# mb.net
KiCad netlist of a schematic drawn in EAGLE
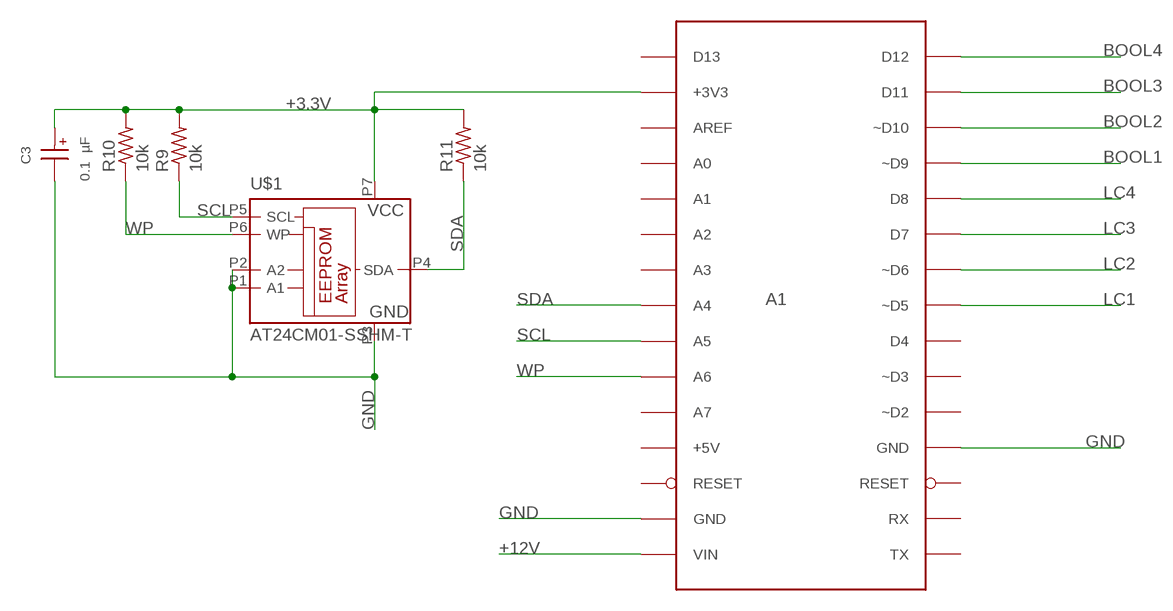
[diagram p0: schematic, sheet 1]
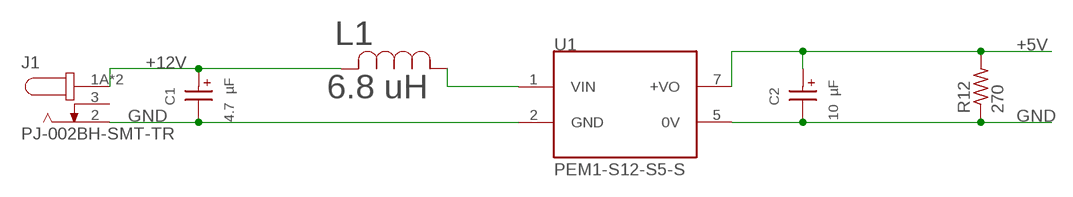
[diagram p1: schematic, sheet 2]
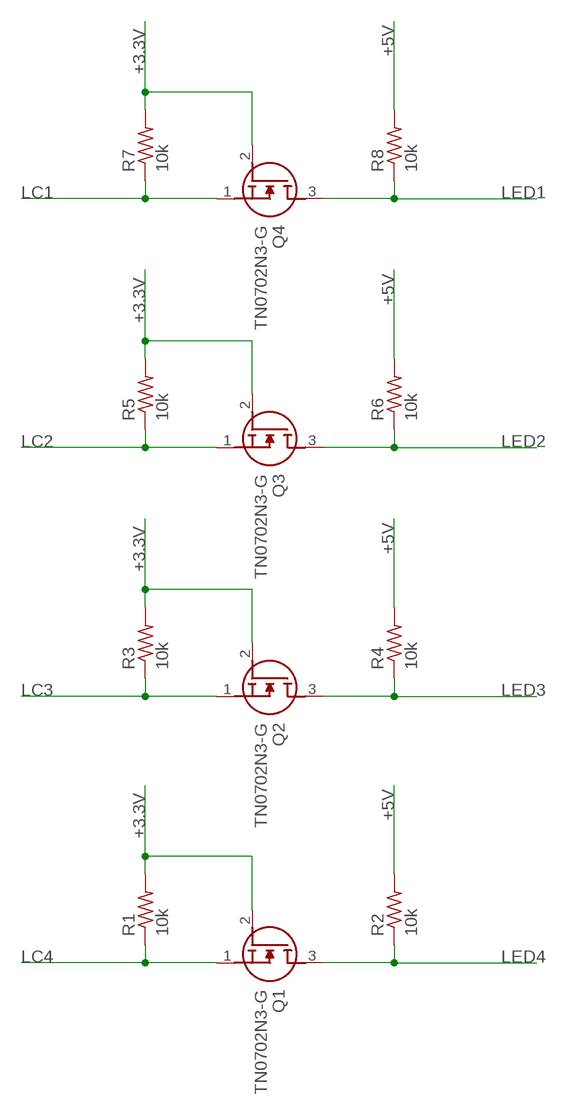
[diagram p2: schematic, sheet 3]
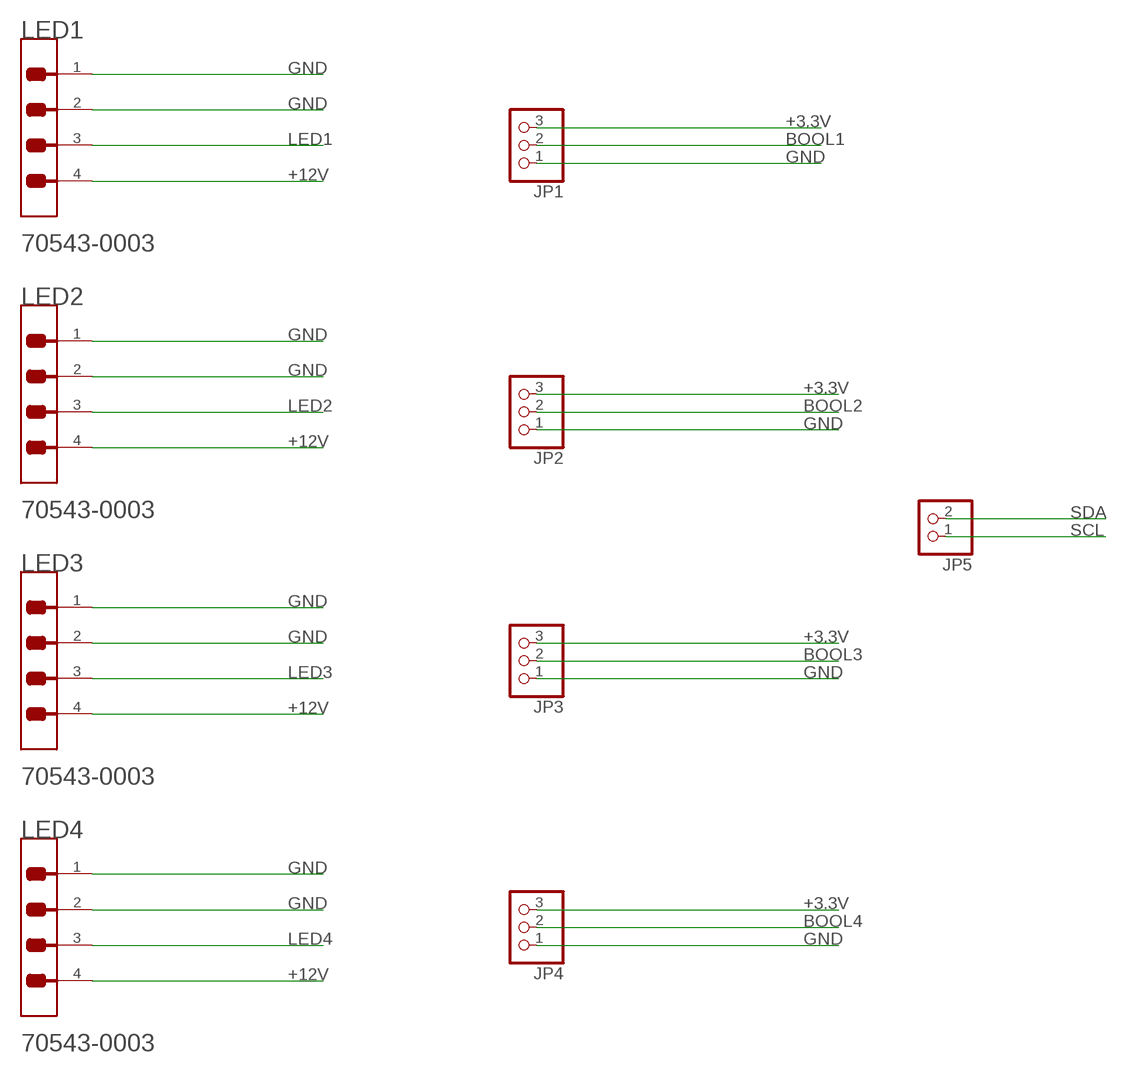
[diagram p3: schematic, sheet 4]

(export (version "E")
  (design (tool "Eeschema 10.0.6"))
  (components
    (comp (ref "Q1")
      (value "TN0702N3-G")
      (footprint "eagle-import:LND150N3-G")
      (fields (field (name "MOUSER_PART_NUMBER") "689-TN0702N3-G"))
      (libsource (lib "eagle-import") (part "TN0702N3-G"))
    )
    (comp (ref "Q2")
      (value "TN0702N3-G")
      (footprint "eagle-import:LND150N3-G")
      (fields (field (name "MOUSER_PART_NUMBER") "689-TN0702N3-G"))
      (libsource (lib "eagle-import") (part "TN0702N3-G"))
    )
    (comp (ref "Q3")
      (value "TN0702N3-G")
      (footprint "eagle-import:LND150N3-G")
      (fields (field (name "MOUSER_PART_NUMBER") "689-TN0702N3-G"))
      (libsource (lib "eagle-import") (part "TN0702N3-G"))
    )
    (comp (ref "Q4")
      (value "TN0702N3-G")
      (footprint "eagle-import:LND150N3-G")
      (fields (field (name "MOUSER_PART_NUMBER") "689-TN0702N3-G"))
      (libsource (lib "eagle-import") (part "TN0702N3-G"))
    )
    (comp (ref "R1")
      (value "10k")
      (footprint "eagle-import:CFR-25")
      (libsource (lib "eagle-import") (part "YAGEO-CFR-25"))
    )
    (comp (ref "R2")
      (value "10k")
      (footprint "eagle-import:CFR-25")
      (libsource (lib "eagle-import") (part "YAGEO-CFR-25"))
    )
    (comp (ref "R3")
      (value "10k")
      (footprint "eagle-import:CFR-25")
      (libsource (lib "eagle-import") (part "YAGEO-CFR-25"))
    )
    (comp (ref "R4")
      (value "10k")
      (footprint "eagle-import:CFR-25")
      (libsource (lib "eagle-import") (part "YAGEO-CFR-25"))
    )
    (comp (ref "R5")
      (value "10k")
      (footprint "eagle-import:CFR-25")
      (libsource (lib "eagle-import") (part "YAGEO-CFR-25"))
    )
    (comp (ref "R6")
      (value "10k")
      (footprint "eagle-import:CFR-25")
      (libsource (lib "eagle-import") (part "YAGEO-CFR-25"))
    )
    (comp (ref "R7")
      (value "10k")
      (footprint "eagle-import:CFR-25")
      (libsource (lib "eagle-import") (part "YAGEO-CFR-25"))
    )
    (comp (ref "R8")
      (value "10k")
      (footprint "eagle-import:CFR-25")
      (libsource (lib "eagle-import") (part "YAGEO-CFR-25"))
    )
    (comp (ref "C1")
      (value "4.7 µF")
      (footprint "eagle-import:WCAP-ATG5_5X11(DXL)")
      (libsource (lib "eagle-import") (part "WCAP-ATG5_5X11_860020672008"))
    )
    (comp (ref "C2")
      (value "10 µF")
      (footprint "eagle-import:WCAP-ATG5_5X11(DXL)")
      (libsource (lib "eagle-import") (part "WCAP-ATG5_5X11_860020672010"))
    )
    (comp (ref "J1")
      (value "PJ-002BH-SMT-TR")
      (footprint "eagle-import:CUI_PJ-002BH-SMT-TR")
      (fields (field (name "MANUFACTURER") "CUI INC"))
      (libsource (lib "eagle-import") (part "PJ-002BH-SMT-TR"))
    )
    (comp (ref "L1")
      (value "6.8 uH")
      (footprint "eagle-import:RL622_SERIES")
      (fields (field (name "MANUFACTURER_PART_NUMBER") "RL622-4R7K-RC"))
      (libsource (lib "eagle-import") (part "RL622-6R8K-RC"))
    )
    (comp (ref "R12")
      (value "270")
      (footprint "eagle-import:CFR-25")
      (libsource (lib "eagle-import") (part "YAGEO-CFR-25"))
    )
    (comp (ref "U1")
      (value "PEM1-S12-S5-S")
      (footprint "eagle-import:CONV_PEM1-S12-S5-S")
      (fields (field (name "MF") "CUI") (field (name "MP") "PEM1-S12-S12-S"))
      (libsource (lib "eagle-import") (part "PEM1-S12-S5-S"))
    )
    (comp (ref "A1")
      (value "NANO_33_IOTNANO_EVERY_SMD")
      (footprint "eagle-import:NANO_EVERY_SMD_PADS")
      (libsource (lib "eagle-import") (part "NANO_33_IOTNANO_EVERY_SMD"))
    )
    (comp (ref "C3")
      (value "0.1 µF")
      (footprint "eagle-import:WCAP-ATG5_5X11(DXL)")
      (libsource (lib "eagle-import") (part "WCAP-ATG5_5X11_860020672001"))
    )
    (comp (ref "R9")
      (value "10k")
      (footprint "eagle-import:CFR-25")
      (libsource (lib "eagle-import") (part "YAGEO-CFR-25"))
    )
    (comp (ref "R10")
      (value "10k")
      (footprint "eagle-import:CFR-25")
      (libsource (lib "eagle-import") (part "YAGEO-CFR-25"))
    )
    (comp (ref "R11")
      (value "10k")
      (footprint "eagle-import:CFR-25")
      (libsource (lib "eagle-import") (part "YAGEO-CFR-25"))
    )
    (comp (ref "U$1")
      (value "AT24CM01-SSHM-T")
      (footprint "eagle-import:8-SOIC(3.9MM)")
      (libsource (lib "eagle-import") (part "AT24CM01-SSHM-T"))
    )
    (comp (ref "JP1")
      (value "PINHD-1X3/90")
      (footprint "eagle-import:1X03_90")
      (libsource (lib "eagle-import") (part "PINHD-1X3/90"))
    )
    (comp (ref "JP2")
      (value "PINHD-1X3/90")
      (footprint "eagle-import:1X03_90")
      (libsource (lib "eagle-import") (part "PINHD-1X3/90"))
    )
    (comp (ref "JP3")
      (value "PINHD-1X3/90")
      (footprint "eagle-import:1X03_90")
      (libsource (lib "eagle-import") (part "PINHD-1X3/90"))
    )
    (comp (ref "JP4")
      (value "PINHD-1X3/90")
      (footprint "eagle-import:1X03_90")
      (libsource (lib "eagle-import") (part "PINHD-1X3/90"))
    )
    (comp (ref "JP5")
      (value "PINHD-1X2")
      (footprint "eagle-import:1X02")
      (libsource (lib "eagle-import") (part "PINHD-1X2"))
    )
    (comp (ref "LED1")
      (value "MOLEX_70543-0003MOLEX_70543-0003_0_0")
      (footprint "eagle-import:MOLEX_70543-0003_0")
      (fields
        (field (name "DIGIKEY_PART_NUMBER") "WM4802-ND")
        (field (name "MF") "Molex")
        (field (name "MOUSER_PART_NUMBER") "538-70543-0003")
      )
      (libsource (lib "eagle-import") (part "MOLEX_70543-0003MOLEX_70543-0003_0_0"))
    )
    (comp (ref "LED2")
      (value "MOLEX_70543-0003MOLEX_70543-0003_0_0")
      (footprint "eagle-import:MOLEX_70543-0003_0")
      (fields
        (field (name "DIGIKEY_PART_NUMBER") "WM4802-ND")
        (field (name "MF") "Molex")
        (field (name "MOUSER_PART_NUMBER") "538-70543-0003")
      )
      (libsource (lib "eagle-import") (part "MOLEX_70543-0003MOLEX_70543-0003_0_0"))
    )
    (comp (ref "LED3")
      (value "MOLEX_70543-0003MOLEX_70543-0003_0_0")
      (footprint "eagle-import:MOLEX_70543-0003_0")
      (fields
        (field (name "DIGIKEY_PART_NUMBER") "WM4802-ND")
        (field (name "MF") "Molex")
        (field (name "MOUSER_PART_NUMBER") "538-70543-0003")
      )
      (libsource (lib "eagle-import") (part "MOLEX_70543-0003MOLEX_70543-0003_0_0"))
    )
    (comp (ref "LED4")
      (value "MOLEX_70543-0003MOLEX_70543-0003_0_0")
      (footprint "eagle-import:MOLEX_70543-0003_0")
      (fields
        (field (name "DIGIKEY_PART_NUMBER") "WM4802-ND")
        (field (name "MF") "Molex")
        (field (name "MOUSER_PART_NUMBER") "538-70543-0003")
      )
      (libsource (lib "eagle-import") (part "MOLEX_70543-0003MOLEX_70543-0003_0_0"))
    )
  )
  (nets
    (net (code "1") (name "+3.3V") (class "Default")
      (node (ref "A1") (pin "+3.3V") (pinfunction "+3V3_+3.3V") (pintype "output"))
      (node (ref "C3") (pin "1") (pinfunction "+_1") (pintype "passive"))
      (node (ref "JP1") (pin "3") (pinfunction "3_3") (pintype "passive"))
      (node (ref "JP2") (pin "3") (pinfunction "3_3") (pintype "passive"))
      (node (ref "JP3") (pin "3") (pinfunction "3_3") (pintype "passive"))
      (node (ref "JP4") (pin "3") (pinfunction "3_3") (pintype "passive"))
      (node (ref "Q1") (pin "2") (pinfunction "G_2") (pintype "bidirectional"))
      (node (ref "Q2") (pin "2") (pinfunction "G_2") (pintype "bidirectional"))
      (node (ref "Q3") (pin "2") (pinfunction "G_2") (pintype "bidirectional"))
      (node (ref "Q4") (pin "2") (pinfunction "G_2") (pintype "bidirectional"))
      (node (ref "R1") (pin "P$2") (pinfunction "2_P$2") (pintype "passive"))
      (node (ref "R10") (pin "P$2") (pinfunction "2_P$2") (pintype "passive"))
      (node (ref "R11") (pin "P$2") (pinfunction "2_P$2") (pintype "passive"))
      (node (ref "R3") (pin "P$2") (pinfunction "2_P$2") (pintype "passive"))
      (node (ref "R5") (pin "P$2") (pinfunction "2_P$2") (pintype "passive"))
      (node (ref "R7") (pin "P$2") (pinfunction "2_P$2") (pintype "passive"))
      (node (ref "R9") (pin "P$2") (pinfunction "2_P$2") (pintype "passive"))
      (node (ref "U$1") (pin "P7") (pinfunction "VCC_P7") (pintype "power_in"))
    )
    (net (code "2") (name "+5V") (class "Default")
      (node (ref "C2") (pin "1") (pinfunction "+_1") (pintype "passive"))
      (node (ref "R12") (pin "P$2") (pinfunction "2_P$2") (pintype "passive"))
      (node (ref "R2") (pin "P$2") (pinfunction "2_P$2") (pintype "passive"))
      (node (ref "R4") (pin "P$2") (pinfunction "2_P$2") (pintype "passive"))
      (node (ref "R6") (pin "P$2") (pinfunction "2_P$2") (pintype "passive"))
      (node (ref "R8") (pin "P$2") (pinfunction "2_P$2") (pintype "passive"))
      (node (ref "U1") (pin "7") (pinfunction "+VO_7") (pintype "output"))
    )
    (net (code "3") (name "+12V") (class "Default")
      (node (ref "A1") (pin "VIN") (pinfunction "VIN_VIN") (pintype "power_in"))
      (node (ref "C1") (pin "1") (pinfunction "+_1") (pintype "passive"))
      (node (ref "J1") (pin "1A") (pinfunction "1_1A") (pintype "passive"))
      (node (ref "J1") (pin "1B") (pinfunction "1_1B") (pintype "passive"))
      (node (ref "L1") (pin "2") (pinfunction "2_2") (pintype "passive"))
      (node (ref "LED1") (pin "4") (pinfunction "4_4") (pintype "bidirectional"))
      (node (ref "LED2") (pin "4") (pinfunction "4_4") (pintype "bidirectional"))
      (node (ref "LED3") (pin "4") (pinfunction "4_4") (pintype "bidirectional"))
      (node (ref "LED4") (pin "4") (pinfunction "4_4") (pintype "bidirectional"))
    )
    (net (code "4") (name "BOOL1") (class "Default")
      (node (ref "A1") (pin "D9") (pinfunction "~{D9}_D9") (pintype "bidirectional"))
      (node (ref "JP1") (pin "2") (pinfunction "2_2") (pintype "passive"))
    )
    (net (code "5") (name "BOOL2") (class "Default")
      (node (ref "A1") (pin "D10") (pinfunction "~{D10}_D10") (pintype "bidirectional"))
      (node (ref "JP2") (pin "2") (pinfunction "2_2") (pintype "passive"))
    )
    (net (code "6") (name "BOOL3") (class "Default")
      (node (ref "A1") (pin "D11") (pinfunction "D11_D11") (pintype "bidirectional"))
      (node (ref "JP3") (pin "2") (pinfunction "2_2") (pintype "passive"))
    )
    (net (code "7") (name "BOOL4") (class "Default")
      (node (ref "A1") (pin "D12") (pinfunction "D12_D12") (pintype "bidirectional"))
      (node (ref "JP4") (pin "2") (pinfunction "2_2") (pintype "passive"))
    )
    (net (code "8") (name "GND") (class "Default")
      (node (ref "A1") (pin "GND@1") (pinfunction "GND_GND@1") (pintype "bidirectional"))
      (node (ref "A1") (pin "GND@2") (pinfunction "GND_GND@2") (pintype "bidirectional"))
      (node (ref "C1") (pin "2") (pinfunction "-_2") (pintype "passive"))
      (node (ref "C2") (pin "2") (pinfunction "-_2") (pintype "passive"))
      (node (ref "C3") (pin "2") (pinfunction "-_2") (pintype "passive"))
      (node (ref "J1") (pin "2") (pinfunction "2_2") (pintype "passive"))
      (node (ref "JP1") (pin "1") (pinfunction "1_1") (pintype "passive"))
      (node (ref "JP2") (pin "1") (pinfunction "1_1") (pintype "passive"))
      (node (ref "JP3") (pin "1") (pinfunction "1_1") (pintype "passive"))
      (node (ref "JP4") (pin "1") (pinfunction "1_1") (pintype "passive"))
      (node (ref "LED1") (pin "1") (pinfunction "1_1") (pintype "bidirectional"))
      (node (ref "LED1") (pin "2") (pinfunction "2_2") (pintype "bidirectional"))
      (node (ref "LED2") (pin "1") (pinfunction "1_1") (pintype "bidirectional"))
      (node (ref "LED2") (pin "2") (pinfunction "2_2") (pintype "bidirectional"))
      (node (ref "LED3") (pin "1") (pinfunction "1_1") (pintype "bidirectional"))
      (node (ref "LED3") (pin "2") (pinfunction "2_2") (pintype "bidirectional"))
      (node (ref "LED4") (pin "1") (pinfunction "1_1") (pintype "bidirectional"))
      (node (ref "LED4") (pin "2") (pinfunction "2_2") (pintype "bidirectional"))
      (node (ref "R12") (pin "P$1") (pinfunction "1_P$1") (pintype "passive"))
      (node (ref "U$1") (pin "P1") (pinfunction "A1_P1") (pintype "input"))
      (node (ref "U$1") (pin "P2") (pinfunction "A2_P2") (pintype "input"))
      (node (ref "U$1") (pin "P3") (pinfunction "GND_P3") (pintype "power_in"))
      (node (ref "U1") (pin "2") (pinfunction "GND_2") (pintype "power_in"))
      (node (ref "U1") (pin "5") (pinfunction "0V_5") (pintype "power_in"))
    )
    (net (code "9") (name "LC1") (class "Default")
      (node (ref "A1") (pin "D5") (pinfunction "~{D5}_D5") (pintype "bidirectional"))
      (node (ref "Q4") (pin "1") (pinfunction "S_1") (pintype "bidirectional"))
      (node (ref "R7") (pin "P$1") (pinfunction "1_P$1") (pintype "passive"))
    )
    (net (code "10") (name "LC2") (class "Default")
      (node (ref "A1") (pin "D6") (pinfunction "~{D6}_D6") (pintype "bidirectional"))
      (node (ref "Q3") (pin "1") (pinfunction "S_1") (pintype "bidirectional"))
      (node (ref "R5") (pin "P$1") (pinfunction "1_P$1") (pintype "passive"))
    )
    (net (code "11") (name "LC3") (class "Default")
      (node (ref "A1") (pin "D7") (pinfunction "D7_D7") (pintype "bidirectional"))
      (node (ref "Q2") (pin "1") (pinfunction "S_1") (pintype "bidirectional"))
      (node (ref "R3") (pin "P$1") (pinfunction "1_P$1") (pintype "passive"))
    )
    (net (code "12") (name "LC4") (class "Default")
      (node (ref "A1") (pin "D8") (pinfunction "D8_D8") (pintype "bidirectional"))
      (node (ref "Q1") (pin "1") (pinfunction "S_1") (pintype "bidirectional"))
      (node (ref "R1") (pin "P$1") (pinfunction "1_P$1") (pintype "passive"))
    )
    (net (code "13") (name "LED1") (class "Default")
      (node (ref "LED1") (pin "3") (pinfunction "3_3") (pintype "bidirectional"))
      (node (ref "Q4") (pin "3") (pinfunction "D_3") (pintype "bidirectional"))
      (node (ref "R8") (pin "P$1") (pinfunction "1_P$1") (pintype "passive"))
    )
    (net (code "14") (name "LED2") (class "Default")
      (node (ref "LED2") (pin "3") (pinfunction "3_3") (pintype "bidirectional"))
      (node (ref "Q3") (pin "3") (pinfunction "D_3") (pintype "bidirectional"))
      (node (ref "R6") (pin "P$1") (pinfunction "1_P$1") (pintype "passive"))
    )
    (net (code "15") (name "LED3") (class "Default")
      (node (ref "LED3") (pin "3") (pinfunction "3_3") (pintype "bidirectional"))
      (node (ref "Q2") (pin "3") (pinfunction "D_3") (pintype "bidirectional"))
      (node (ref "R4") (pin "P$1") (pinfunction "1_P$1") (pintype "passive"))
    )
    (net (code "16") (name "LED4") (class "Default")
      (node (ref "LED4") (pin "3") (pinfunction "3_3") (pintype "bidirectional"))
      (node (ref "Q1") (pin "3") (pinfunction "D_3") (pintype "bidirectional"))
      (node (ref "R2") (pin "P$1") (pinfunction "1_P$1") (pintype "passive"))
    )
    (net (code "17") (name "Net-(U1-VIN)") (class "Default")
      (node (ref "L1") (pin "1") (pinfunction "1_1") (pintype "passive"))
      (node (ref "U1") (pin "1") (pinfunction "VIN_1") (pintype "input"))
    )
    (net (code "18") (name "SCL") (class "Default")
      (node (ref "A1") (pin "A5") (pinfunction "A5_A5") (pintype "bidirectional"))
      (node (ref "JP5") (pin "1") (pinfunction "1_1") (pintype "passive"))
      (node (ref "R9") (pin "P$1") (pinfunction "1_P$1") (pintype "passive"))
      (node (ref "U$1") (pin "P5") (pinfunction "SCL_P5") (pintype "input"))
    )
    (net (code "19") (name "SDA") (class "Default")
      (node (ref "A1") (pin "A4") (pinfunction "A4_A4") (pintype "bidirectional"))
      (node (ref "JP5") (pin "2") (pinfunction "2_2") (pintype "passive"))
      (node (ref "R11") (pin "P$1") (pinfunction "1_P$1") (pintype "passive"))
      (node (ref "U$1") (pin "P4") (pinfunction "SDA_P4") (pintype "bidirectional"))
    )
    (net (code "20") (name "WP") (class "Default")
      (node (ref "A1") (pin "A6") (pinfunction "A6_A6") (pintype "bidirectional"))
      (node (ref "R10") (pin "P$1") (pinfunction "1_P$1") (pintype "passive"))
      (node (ref "U$1") (pin "P6") (pinfunction "WP_P6") (pintype "input"))
    )
    (net (code "21") (name "unconnected-(A1-Pad+5V)") (class "Default")
      (node (ref "A1") (pin "+5V") (pinfunction "+5V_+5V") (pintype "output"))
    )
    (net (code "22") (name "unconnected-(A1-PadA0)") (class "Default")
      (node (ref "A1") (pin "A0") (pinfunction "A0_A0") (pintype "bidirectional"))
    )
    (net (code "23") (name "unconnected-(A1-PadA1)") (class "Default")
      (node (ref "A1") (pin "A1") (pinfunction "A1_A1") (pintype "bidirectional"))
    )
    (net (code "24") (name "unconnected-(A1-PadA2)") (class "Default")
      (node (ref "A1") (pin "A2") (pinfunction "A2_A2") (pintype "bidirectional"))
    )
    (net (code "25") (name "unconnected-(A1-PadA3)") (class "Default")
      (node (ref "A1") (pin "A3") (pinfunction "A3_A3") (pintype "bidirectional"))
    )
    (net (code "26") (name "unconnected-(A1-PadA7)") (class "Default")
      (node (ref "A1") (pin "A7") (pinfunction "A7_A7") (pintype "bidirectional"))
    )
    (net (code "27") (name "unconnected-(A1-PadAREF)") (class "Default")
      (node (ref "A1") (pin "AREF") (pinfunction "AREF_AREF") (pintype "bidirectional"))
    )
    (net (code "28") (name "unconnected-(A1-PadD4)") (class "Default")
      (node (ref "A1") (pin "D4") (pinfunction "D4_D4") (pintype "bidirectional"))
    )
    (net (code "29") (name "unconnected-(A1-PadD13)") (class "Default")
      (node (ref "A1") (pin "D13") (pinfunction "D13_D13") (pintype "bidirectional"))
    )
    (net (code "30") (name "unconnected-(A1-PadRX)") (class "Default")
      (node (ref "A1") (pin "RX") (pinfunction "RX_RX") (pintype "bidirectional"))
    )
    (net (code "31") (name "unconnected-(A1-PadTX)") (class "Default")
      (node (ref "A1") (pin "TX") (pinfunction "TX_TX") (pintype "bidirectional"))
    )
    (net (code "32") (name "unconnected-(A1-RESET-PadRESET@1)") (class "Default")
      (node (ref "A1") (pin "RESET@1") (pinfunction "RESET_RESET@1") (pintype "input"))
    )
    (net (code "33") (name "unconnected-(A1-RESET-PadRESET@2)") (class "Default")
      (node (ref "A1") (pin "RESET@2") (pinfunction "RESET_RESET@2") (pintype "input"))
    )
    (net (code "34") (name "unconnected-(A1-~{D2}-PadD2)") (class "Default")
      (node (ref "A1") (pin "D2") (pinfunction "~{D2}_D2") (pintype "bidirectional"))
    )
    (net (code "35") (name "unconnected-(A1-~{D3}-PadD3)") (class "Default")
      (node (ref "A1") (pin "D3") (pinfunction "~{D3}_D3") (pintype "bidirectional"))
    )
    (net (code "36") (name "unconnected-(J1-Pad3)") (class "Default")
      (node (ref "J1") (pin "3") (pinfunction "3_3") (pintype "passive"))
    )
  )
)
